# Microcontrolador.net
KiCad netlist of a schematic drawn in Altium Designer
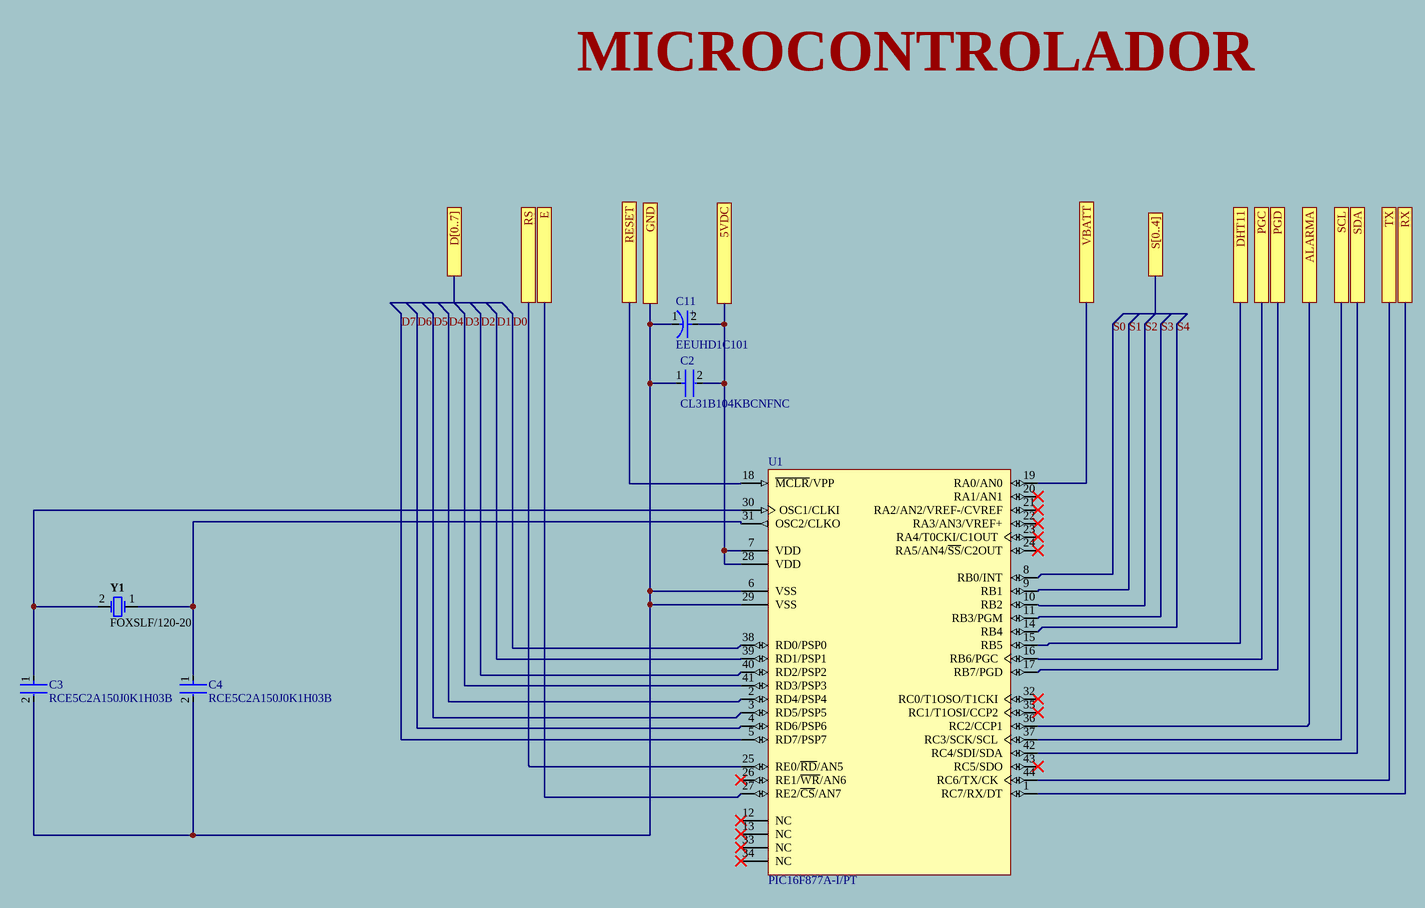
[diagram p0: Microcontrolador.SchDoc]

(export (version "E")
  (design (tool "Eeschema 10.0.6"))
  (components
    (comp (ref "C2")
      (value "CL31B104KBCNFNC")
      (footprint "FP-CL31-IPC_C")
      (description "Cap Ceramic 100nF 50V X7R ±10% SMD 1206 +125°C Embossed T/R")
      (fields (field (name "TOLERANCE") "10%"))
      (libsource (lib "Altium Content Vault") (part "b4654b650e69147ec39a6b967a45e02"))
    )
    (comp (ref "C3")
      (value "RCE5C2A150J0K1H03B")
      (footprint "FP-RCE0K1-MFG")
      (description "Cap Ceramic 15pF 100V C0G ±5% Radial 5mm +125°C Automotive Bulk")
      (fields (field (name "TOLERANCE") "5%"))
      (libsource (lib "Altium Content Vault") (part "b4654b650e69147ec39a6b967a45e02"))
    )
    (comp (ref "C4")
      (value "RCE5C2A150J0K1H03B")
      (footprint "FP-RCE0K1-MFG")
      (description "Cap Ceramic 15pF 100V C0G ±5% Radial 5mm +125°C Automotive Bulk")
      (fields (field (name "TOLERANCE") "5%"))
      (libsource (lib "Altium Content Vault") (part "b4654b650e69147ec39a6b967a45e02"))
    )
    (comp (ref "C11")
      (value "EEUHD1C101")
      (footprint "FP-RAD-TH-D_5_0_5-L_11_1-MFG")
      (description "Aluminum Electrolytic Capacitors (Radial Lead Type) AEC-Q200 Qualified 100uF ±20% 16V")
      (fields (field (name "TOLERANCE") "20%") (field (name "VOLTAGE") "16V"))
      (libsource (lib "Altium Content Vault") (part "a00bbbee19879c290e62620ae7e47b1"))
    )
    (comp (ref "U1")
      (value "PIC16F877A-I/PT")
      (footprint "TQFP-PT44_M")
      (libsource (lib "Altium Content Vault") (part "MC-8B-16F874A-SQ44B"))
    )
    (comp (ref "Y1")
      (value "FOXSLF/120-20")
      (footprint "FOX-FOXSLF-2_V")
      (description "Resistance Weld Thru-Hole Crystal, 12 MHz, +/-30 ppm, -20 to 70 degC, 2-Pin THD, RoHS, Bulk")
      (libsource (lib "Altium Content Vault") (part "XTAL-1-2-2"))
    )
  )
  (nets
    (net (code "1") (name "/5VDC") (class "Default")
      (node (ref "C11") (pin "2") (pinfunction "A_2") (pintype "passive"))
      (node (ref "C2") (pin "2") (pinfunction "2_2") (pintype "passive"))
      (node (ref "U1") (pin "28") (pinfunction "VDD_28") (pintype "power_in"))
      (node (ref "U1") (pin "7") (pinfunction "VDD_7") (pintype "power_in"))
    )
    (net (code "2") (name "/ALARMA") (class "Default")
      (node (ref "U1") (pin "36") (pinfunction "RC2/CCP1_36") (pintype "bidirectional"))
    )
    (net (code "3") (name "/D0") (class "Default")
      (node (ref "U1") (pin "38") (pinfunction "RD0/PSP0_38") (pintype "bidirectional"))
    )
    (net (code "4") (name "/D1") (class "Default")
      (node (ref "U1") (pin "39") (pinfunction "RD1/PSP1_39") (pintype "bidirectional"))
    )
    (net (code "5") (name "/D2") (class "Default")
      (node (ref "U1") (pin "40") (pinfunction "RD2/PSP2_40") (pintype "bidirectional"))
    )
    (net (code "6") (name "/D3") (class "Default")
      (node (ref "U1") (pin "41") (pinfunction "RD3/PSP3_41") (pintype "bidirectional"))
    )
    (net (code "7") (name "/D4") (class "Default")
      (node (ref "U1") (pin "2") (pinfunction "RD4/PSP4_2") (pintype "bidirectional"))
    )
    (net (code "8") (name "/D5") (class "Default")
      (node (ref "U1") (pin "3") (pinfunction "RD5/PSP5_3") (pintype "bidirectional"))
    )
    (net (code "9") (name "/D6") (class "Default")
      (node (ref "U1") (pin "4") (pinfunction "RD6/PSP6_4") (pintype "bidirectional"))
    )
    (net (code "10") (name "/D7") (class "Default")
      (node (ref "U1") (pin "5") (pinfunction "RD7/PSP7_5") (pintype "bidirectional"))
    )
    (net (code "11") (name "/DHT11") (class "Default")
      (node (ref "U1") (pin "15") (pinfunction "RB5_15") (pintype "bidirectional"))
    )
    (net (code "13") (name "/E") (class "Default")
      (node (ref "U1") (pin "27") (pinfunction "RE2/~{CS}/AN7_27") (pintype "bidirectional"))
    )
    (net (code "14") (name "/GND") (class "Default")
      (node (ref "C11") (pin "1") (pinfunction "C_1") (pintype "passive"))
      (node (ref "C2") (pin "1") (pinfunction "1_1") (pintype "passive"))
      (node (ref "C3") (pin "2") (pinfunction "2_2") (pintype "passive"))
      (node (ref "C4") (pin "2") (pinfunction "2_2") (pintype "passive"))
      (node (ref "U1") (pin "29") (pinfunction "VSS_29") (pintype "power_in"))
      (node (ref "U1") (pin "6") (pinfunction "VSS_6") (pintype "power_in"))
    )
    (net (code "15") (name "/PGC") (class "Default")
      (node (ref "U1") (pin "16") (pinfunction "RB6/PGC_16") (pintype "bidirectional"))
    )
    (net (code "16") (name "/PGD") (class "Default")
      (node (ref "U1") (pin "17") (pinfunction "RB7/PGD_17") (pintype "bidirectional"))
    )
    (net (code "17") (name "/RESET") (class "Default")
      (node (ref "U1") (pin "18") (pinfunction "~{MCLR}/VPP_18") (pintype "input"))
    )
    (net (code "18") (name "/RS") (class "Default")
      (node (ref "U1") (pin "25") (pinfunction "RE0/~{RD}/AN5_25") (pintype "bidirectional"))
    )
    (net (code "19") (name "/RX") (class "Default")
      (node (ref "U1") (pin "1") (pinfunction "RC7/RX/DT_1") (pintype "bidirectional"))
    )
    (net (code "20") (name "/S0") (class "Default")
      (node (ref "U1") (pin "8") (pinfunction "RB0/INT_8") (pintype "bidirectional"))
    )
    (net (code "21") (name "/S1") (class "Default")
      (node (ref "U1") (pin "9") (pinfunction "RB1_9") (pintype "bidirectional"))
    )
    (net (code "22") (name "/S2") (class "Default")
      (node (ref "U1") (pin "10") (pinfunction "RB2_10") (pintype "bidirectional"))
    )
    (net (code "23") (name "/S3") (class "Default")
      (node (ref "U1") (pin "11") (pinfunction "RB3/PGM_11") (pintype "bidirectional"))
    )
    (net (code "24") (name "/S4") (class "Default")
      (node (ref "U1") (pin "14") (pinfunction "RB4_14") (pintype "bidirectional"))
    )
    (net (code "25") (name "/SCL") (class "Default")
      (node (ref "U1") (pin "37") (pinfunction "RC3/SCK/SCL_37") (pintype "bidirectional"))
    )
    (net (code "26") (name "/SDA") (class "Default")
      (node (ref "U1") (pin "42") (pinfunction "RC4/SDI/SDA_42") (pintype "bidirectional"))
    )
    (net (code "28") (name "/TX") (class "Default")
      (node (ref "U1") (pin "44") (pinfunction "RC6/TX/CK_44") (pintype "bidirectional"))
    )
    (net (code "29") (name "/VBATT") (class "Default")
      (node (ref "U1") (pin "19") (pinfunction "RA0/AN0_19") (pintype "bidirectional"))
    )
    (net (code "30") (name "Net-(U1-OSC1{slash}CLKI)") (class "Default")
      (node (ref "C3") (pin "1") (pinfunction "1_1") (pintype "passive"))
      (node (ref "U1") (pin "30") (pinfunction "OSC1/CLKI_30") (pintype "input"))
      (node (ref "Y1") (pin "2") (pinfunction "2_2") (pintype "passive"))
    )
    (net (code "31") (name "Net-(U1-OSC2{slash}CLKO)") (class "Default")
      (node (ref "C4") (pin "1") (pinfunction "1_1") (pintype "passive"))
      (node (ref "U1") (pin "31") (pinfunction "OSC2/CLKO_31") (pintype "output"))
      (node (ref "Y1") (pin "1") (pinfunction "1_1") (pintype "passive"))
    )
    (net (code "32") (name "unconnected-(U1-NC-Pad12)") (class "Default")
      (node (ref "U1") (pin "12") (pinfunction "NC_12") (pintype "passive+no_connect"))
    )
    (net (code "33") (name "unconnected-(U1-NC-Pad13)") (class "Default")
      (node (ref "U1") (pin "13") (pinfunction "NC_13") (pintype "passive+no_connect"))
    )
    (net (code "34") (name "unconnected-(U1-NC-Pad33)") (class "Default")
      (node (ref "U1") (pin "33") (pinfunction "NC_33") (pintype "passive+no_connect"))
    )
    (net (code "35") (name "unconnected-(U1-NC-Pad34)") (class "Default")
      (node (ref "U1") (pin "34") (pinfunction "NC_34") (pintype "passive+no_connect"))
    )
    (net (code "36") (name "unconnected-(U1-RA1{slash}AN1-Pad20)") (class "Default")
      (node (ref "U1") (pin "20") (pinfunction "RA1/AN1_20") (pintype "bidirectional+no_connect"))
    )
    (net (code "37") (name "unconnected-(U1-RA2{slash}AN2{slash}VREF-{slash}CVREF-Pad21)") (class "Default")
      (node (ref "U1") (pin "21") (pinfunction "RA2/AN2/VREF-/CVREF_21") (pintype "bidirectional+no_connect"))
    )
    (net (code "38") (name "unconnected-(U1-RA3{slash}AN3{slash}VREF+-Pad22)") (class "Default")
      (node (ref "U1") (pin "22") (pinfunction "RA3/AN3/VREF+_22") (pintype "bidirectional+no_connect"))
    )
    (net (code "39") (name "unconnected-(U1-RA4{slash}T0CKI{slash}C1OUT-Pad23)") (class "Default")
      (node (ref "U1") (pin "23") (pinfunction "RA4/T0CKI/C1OUT_23") (pintype "bidirectional+no_connect"))
    )
    (net (code "40") (name "unconnected-(U1-RA5{slash}AN4{slash}~{SS}{slash}C2OUT-Pad24)") (class "Default")
      (node (ref "U1") (pin "24") (pinfunction "RA5/AN4/~{SS}/C2OUT_24") (pintype "bidirectional+no_connect"))
    )
    (net (code "41") (name "unconnected-(U1-RC0{slash}T1OSO{slash}T1CKI-Pad32)") (class "Default")
      (node (ref "U1") (pin "32") (pinfunction "RC0/T1OSO/T1CKI_32") (pintype "bidirectional+no_connect"))
    )
    (net (code "42") (name "unconnected-(U1-RC1{slash}T1OSI{slash}CCP2-Pad35)") (class "Default")
      (node (ref "U1") (pin "35") (pinfunction "RC1/T1OSI/CCP2_35") (pintype "bidirectional+no_connect"))
    )
    (net (code "43") (name "unconnected-(U1-RC5{slash}SDO-Pad43)") (class "Default")
      (node (ref "U1") (pin "43") (pinfunction "RC5/SDO_43") (pintype "bidirectional+no_connect"))
    )
    (net (code "44") (name "unconnected-(U1-RE1{slash}~{WR}{slash}AN6-Pad26)") (class "Default")
      (node (ref "U1") (pin "26") (pinfunction "RE1/~{WR}/AN6_26") (pintype "bidirectional+no_connect"))
    )
  )
)
